# S7CAS-PLEIADES-CARTE-MERE_P07_ETH.net
KiCad netlist of a schematic drawn in Altium Designer
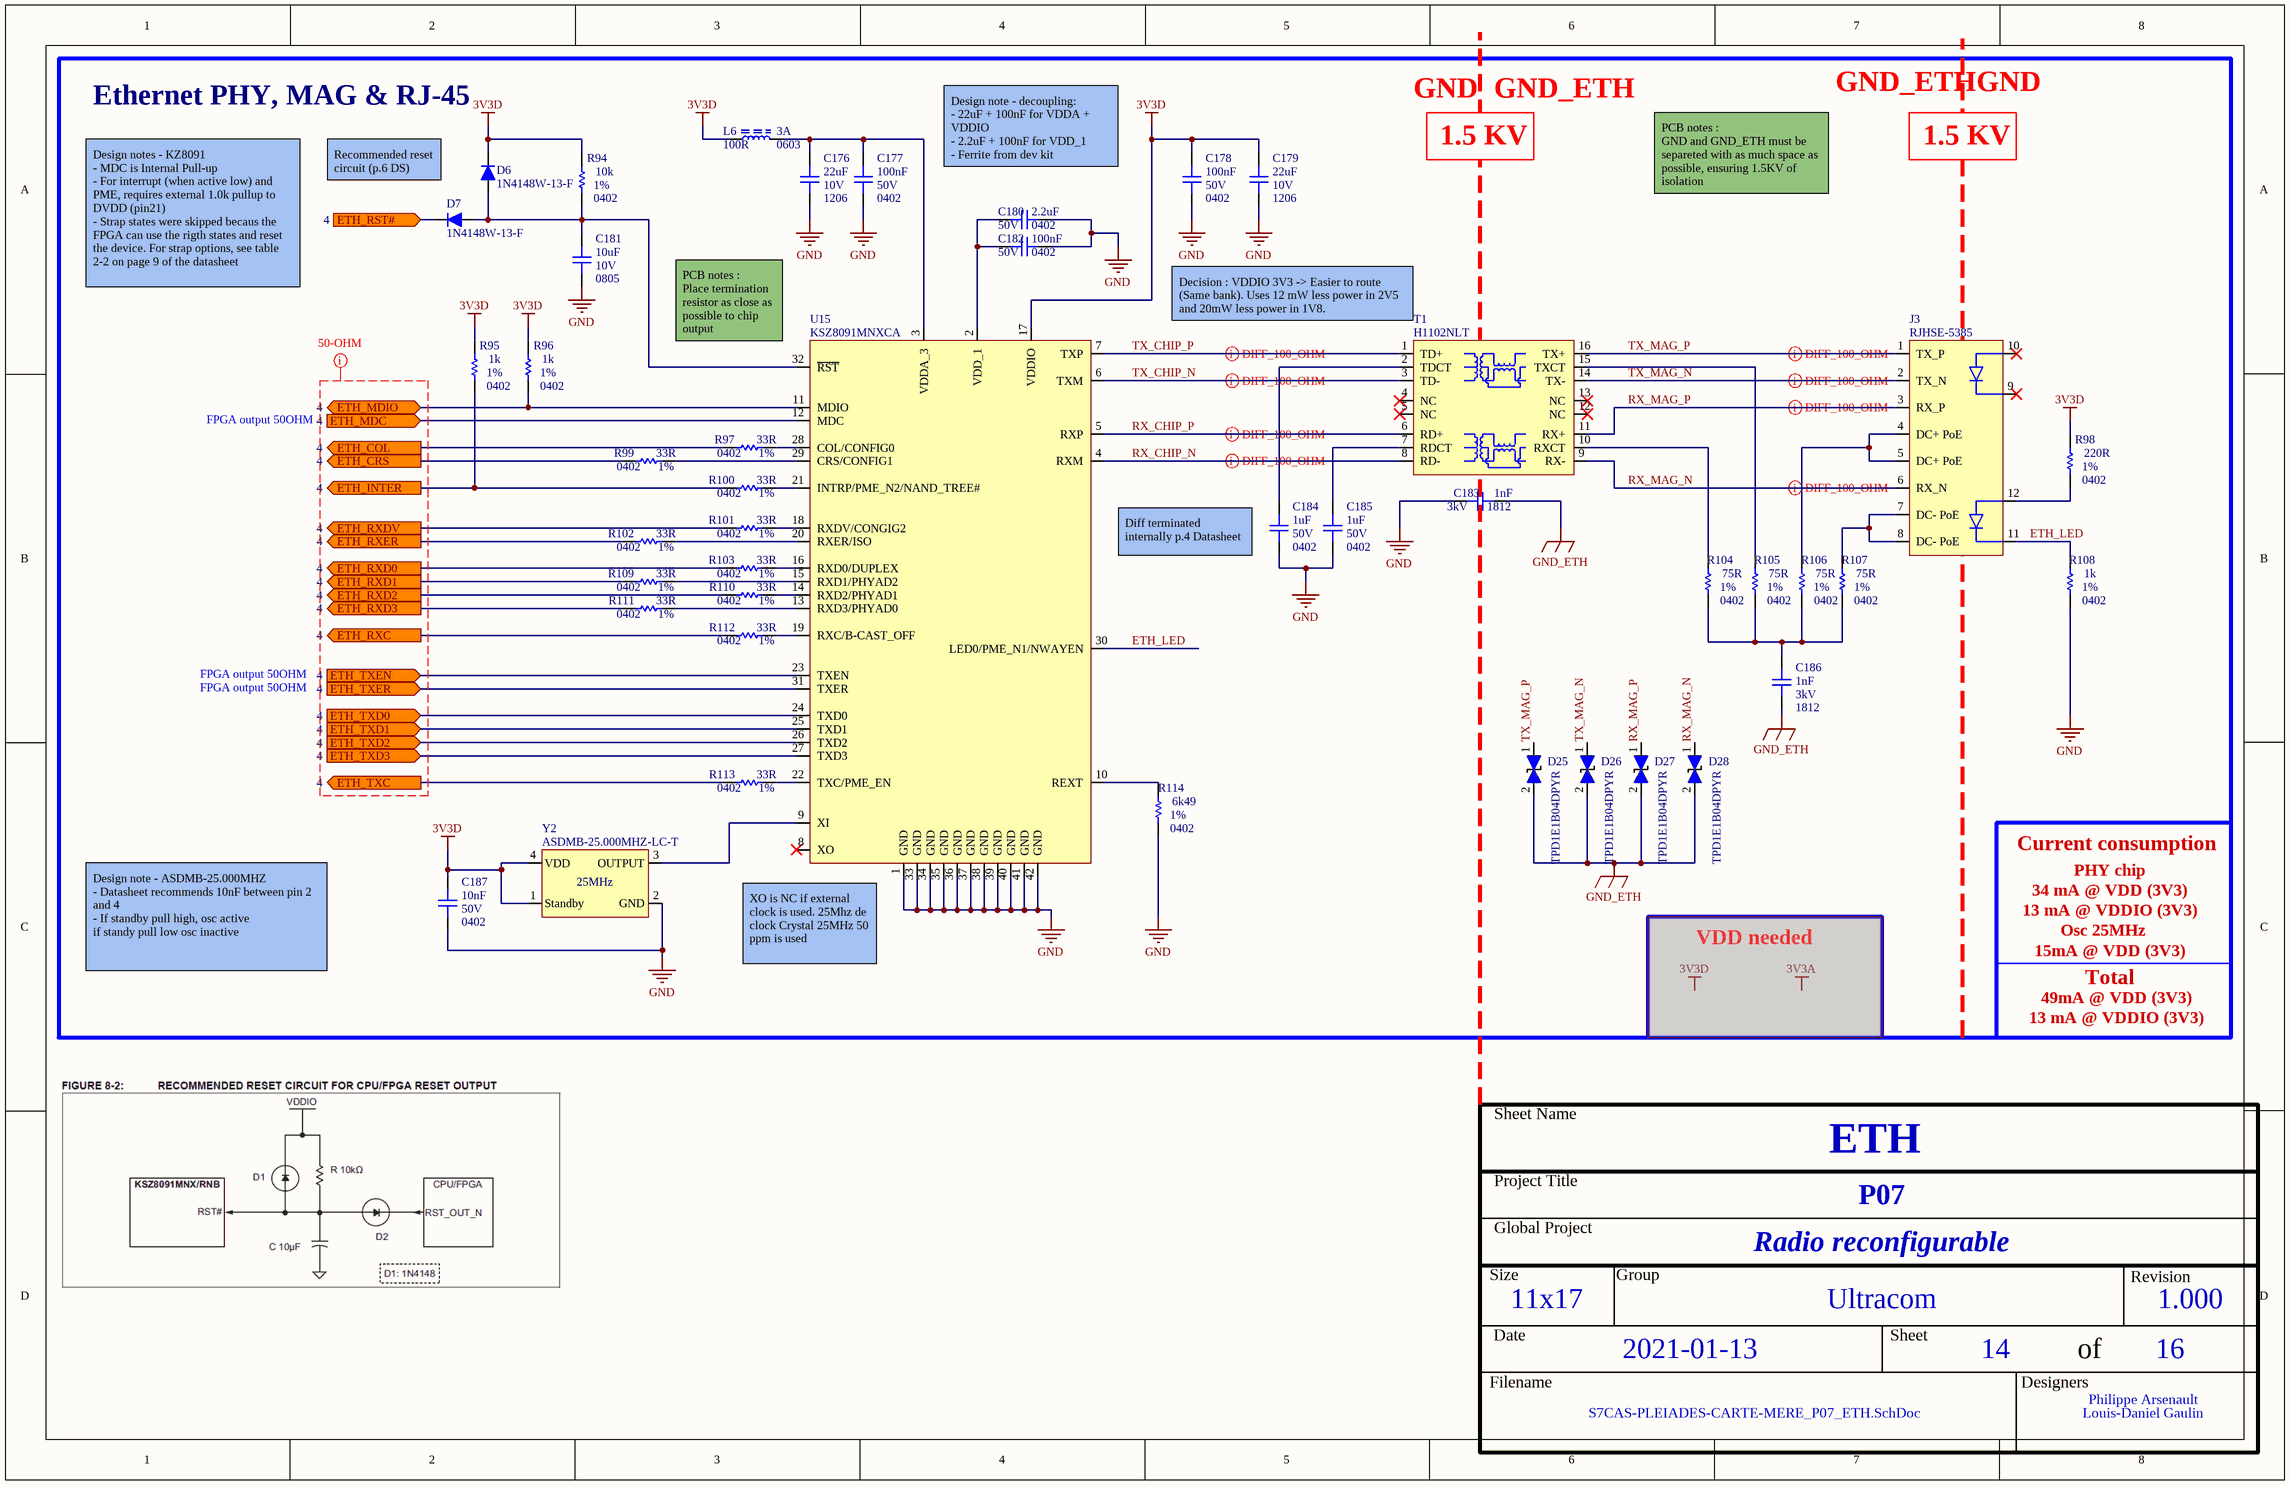
[diagram p0: S7CAS-PLEIADES-CARTE-MERE_P07_ETH.SchDoc]

(export (version "E")
  (design (tool "Eeschema 10.0.6"))
  (components
    (comp (ref "C176")
      (value "22uF")
      (footprint "CAP_1206")
      (description "CAP - 1206")
      (fields
        (field (name "VOLTAGE") "10V")
        (field (name "PACKAGE") "1206")
        (field (name "CREATEDBY") "Jonathan Bouchard")
      )
      (libsource (lib "S7CAS_LIB2021") (part "CAP - 1206"))
    )
    (comp (ref "C177")
      (value "100nF")
      (footprint "CAP_0402")
      (description "CAP - 0402")
      (fields
        (field (name "VOLTAGE") "50V")
        (field (name "PACKAGE") "0402")
        (field (name "CREATEDBY") "Jonathan Bouchard")
      )
      (libsource (lib "S7CAS_LIB2021") (part "CAP - 0402"))
    )
    (comp (ref "C178")
      (value "100nF")
      (footprint "CAP_0402")
      (description "CAP - 0402")
      (fields
        (field (name "VOLTAGE") "50V")
        (field (name "PACKAGE") "0402")
        (field (name "CREATEDBY") "Jonathan Bouchard")
      )
      (libsource (lib "S7CAS_LIB2021") (part "CAP - 0402"))
    )
    (comp (ref "C179")
      (value "22uF")
      (footprint "CAP_1206")
      (description "CAP - 1206")
      (fields
        (field (name "VOLTAGE") "10V")
        (field (name "PACKAGE") "1206")
        (field (name "CREATEDBY") "Jonathan Bouchard")
      )
      (libsource (lib "S7CAS_LIB2021") (part "CAP - 1206"))
    )
    (comp (ref "C180")
      (value "2.2uF")
      (footprint "CAP_0402")
      (description "CAP - 0402")
      (fields
        (field (name "VOLTAGE") "50V")
        (field (name "PACKAGE") "0402")
        (field (name "CREATEDBY") "Jonathan Bouchard")
      )
      (libsource (lib "S7CAS_LIB2021") (part "CAP - 0402"))
    )
    (comp (ref "C181")
      (value "10uF")
      (footprint "CAP_0805")
      (description "CAP - 0805")
      (fields
        (field (name "MFG") "CL21B106KPQNNNE")
        (field (name "VOLTAGE") "10V")
        (field (name "PACKAGE") "0805")
        (field (name "CREATEDBY") "Jonathan Bouchard")
      )
      (libsource (lib "S7CAS_LIB2021") (part "CAP - 0805"))
    )
    (comp (ref "C182")
      (value "100nF")
      (footprint "CAP_0402")
      (description "CAP - 0402")
      (fields
        (field (name "VOLTAGE") "50V")
        (field (name "PACKAGE") "0402")
        (field (name "CREATEDBY") "Jonathan Bouchard")
      )
      (libsource (lib "S7CAS_LIB2021") (part "CAP - 0402"))
    )
    (comp (ref "C183")
      (value "1nF")
      (footprint "CAP_1812")
      (description "CAP - 1812")
      (fields
        (field (name "MFG PART NUMBER") "1812HC102MAT1A")
        (field (name "VOLTAGE") "3kV")
        (field (name "PACKAGE") "1812")
        (field (name "CREATEDBY") "Jonathan Bouchard")
      )
      (libsource (lib "S7CAS_P07") (part "CAP - 1812"))
    )
    (comp (ref "C184")
      (value "1uF")
      (footprint "CAP_0402")
      (description "CAP - 0402")
      (fields
        (field (name "VOLTAGE") "50V")
        (field (name "PACKAGE") "0402")
        (field (name "CREATEDBY") "Jonathan Bouchard")
      )
      (libsource (lib "S7CAS_LIB2021") (part "CAP - 0402"))
    )
    (comp (ref "C185")
      (value "1uF")
      (footprint "CAP_0402")
      (description "CAP - 0402")
      (fields
        (field (name "VOLTAGE") "50V")
        (field (name "PACKAGE") "0402")
        (field (name "CREATEDBY") "Jonathan Bouchard")
      )
      (libsource (lib "S7CAS_LIB2021") (part "CAP - 0402"))
    )
    (comp (ref "C186")
      (value "1nF")
      (footprint "CAP_1812")
      (description "CAP - 1812")
      (fields
        (field (name "MFG PART NUMBER") "1812HC102MAT1A")
        (field (name "VOLTAGE") "3kV")
        (field (name "PACKAGE") "1812")
        (field (name "CREATEDBY") "Jonathan Bouchard")
      )
      (libsource (lib "S7CAS_P07") (part "CAP - 1812"))
    )
    (comp (ref "C187")
      (value "10nF")
      (footprint "CAP_0402")
      (description "CAP - 0402")
      (fields
        (field (name "VOLTAGE") "50V")
        (field (name "PACKAGE") "0402")
        (field (name "CREATEDBY") "Jonathan Bouchard")
      )
      (libsource (lib "S7CAS_LIB2021") (part "CAP - 0402"))
    )
    (comp (ref "D6")
      (value "1N4148W-13-F")
      (footprint "SOD123_DIO")
      (description "1N4148")
      (fields (field (name "COPYRIGHT") "Copyright (C) 2018 Accelerated Designs. All rights reserved"))
      (libsource (lib "S7CAS_P07") (part "DIO_1N4148W-13-F"))
    )
    (comp (ref "D7")
      (value "1N4148W-13-F")
      (footprint "SOD123_DIO")
      (description "1N4148")
      (fields (field (name "COPYRIGHT") "Copyright (C) 2018 Accelerated Designs. All rights reserved"))
      (libsource (lib "S7CAS_P07") (part "DIO_1N4148W-13-F"))
    )
    (comp (ref "D25")
      (value "TPD1E1B04DPYR")
      (footprint "TVS_DATA_TPD1E1B04DPYR")
      (description "TVS - TVS DIODE 3.6V 8.5V - 0402")
      (fields
        (field (name "CREATEDBY/DATE") "Keven Deslandes - 2018/10/19")
        (field (name "VERIFIEDBY") "Caroline Paulin - 28 janv 2019")
      )
      (libsource (lib "S7CAS_LIB2021") (part "TVS_DATA_TPD1E1B04DPYR"))
    )
    (comp (ref "D26")
      (value "TPD1E1B04DPYR")
      (footprint "TVS_DATA_TPD1E1B04DPYR")
      (description "TVS - TVS DIODE 3.6V 8.5V - 0402")
      (fields
        (field (name "CREATEDBY/DATE") "Keven Deslandes - 2018/10/19")
        (field (name "VERIFIEDBY") "Caroline Paulin - 28 janv 2019")
      )
      (libsource (lib "S7CAS_LIB2021") (part "TVS_DATA_TPD1E1B04DPYR"))
    )
    (comp (ref "D27")
      (value "TPD1E1B04DPYR")
      (footprint "TVS_DATA_TPD1E1B04DPYR")
      (description "TVS - TVS DIODE 3.6V 8.5V - 0402")
      (fields
        (field (name "CREATEDBY/DATE") "Keven Deslandes - 2018/10/19")
        (field (name "VERIFIEDBY") "Caroline Paulin - 28 janv 2019")
      )
      (libsource (lib "S7CAS_LIB2021") (part "TVS_DATA_TPD1E1B04DPYR"))
    )
    (comp (ref "D28")
      (value "TPD1E1B04DPYR")
      (footprint "TVS_DATA_TPD1E1B04DPYR")
      (description "TVS - TVS DIODE 3.6V 8.5V - 0402")
      (fields
        (field (name "CREATEDBY/DATE") "Keven Deslandes - 2018/10/19")
        (field (name "VERIFIEDBY") "Caroline Paulin - 28 janv 2019")
      )
      (libsource (lib "S7CAS_LIB2021") (part "TVS_DATA_TPD1E1B04DPYR"))
    )
    (comp (ref "J3")
      (value "RJHSE-5385")
      (footprint "CONN_ETHERNET_RJHSE-5385")
      (description "CONN - MOD JACK RJ45 R/A ETHERNET - TH")
      (fields (field (name "MFG") "Amphenol") (field (name "CREATEDBY") "Jonathan Bouchard"))
      (libsource (lib "S7CAS_LIB2021") (part "CONN_ETHERNET_RJHSE-5385"))
    )
    (comp (ref "L6")
      (value "100R")
      (footprint "FER_0603")
      (description "FER - 0603")
      (fields
        (field (name "CURRENT") "3A")
        (field (name "PACKAGE") "0603")
        (field (name "CREATEDBY") "Jonathan Bouchard")
      )
      (libsource (lib "S7CAS_LIB2021") (part "FER - 0603"))
    )
    (comp (ref "R94")
      (value "10k")
      (footprint "RES_0402")
      (description "RES - 0402")
      (fields
        (field (name "VOLTAGE") "50V")
        (field (name "POWER") "1/16W")
        (field (name "PACKAGE") "0402")
        (field (name "PRECISION") "1%")
        (field (name "CREATEDBY") "Jonathan Bouchard")
      )
      (libsource (lib "S7CAS_LIB2021") (part "RES - 0402"))
    )
    (comp (ref "R95")
      (value "1k")
      (footprint "RES_0402")
      (description "RES - 0402")
      (fields
        (field (name "VOLTAGE") "50V")
        (field (name "POWER") "1/16W")
        (field (name "PACKAGE") "0402")
        (field (name "PRECISION") "1%")
        (field (name "CREATEDBY") "Jonathan Bouchard")
      )
      (libsource (lib "S7CAS_LIB2021") (part "RES - 0402"))
    )
    (comp (ref "R96")
      (value "1k")
      (footprint "RES_0402")
      (description "RES - 0402")
      (fields
        (field (name "VOLTAGE") "50V")
        (field (name "POWER") "1/16W")
        (field (name "PACKAGE") "0402")
        (field (name "PRECISION") "1%")
        (field (name "CREATEDBY") "Jonathan Bouchard")
      )
      (libsource (lib "S7CAS_LIB2021") (part "RES - 0402"))
    )
    (comp (ref "R97")
      (value "33R")
      (footprint "RES_0402")
      (description "RES - 0402")
      (fields
        (field (name "VOLTAGE") "50V")
        (field (name "POWER") "1/16W")
        (field (name "PACKAGE") "0402")
        (field (name "PRECISION") "1%")
        (field (name "CREATEDBY") "Jonathan Bouchard")
      )
      (libsource (lib "S7CAS_LIB2021") (part "RES - 0402"))
    )
    (comp (ref "R98")
      (value "220R")
      (footprint "RES_0402")
      (description "RES - 0402")
      (fields
        (field (name "VOLTAGE") "50V")
        (field (name "POWER") "1/16W")
        (field (name "PACKAGE") "0402")
        (field (name "PRECISION") "1%")
        (field (name "CREATEDBY") "Jonathan Bouchard")
      )
      (libsource (lib "S7CAS_LIB2021") (part "RES - 0402"))
    )
    (comp (ref "R99")
      (value "33R")
      (footprint "RES_0402")
      (description "RES - 0402")
      (fields
        (field (name "VOLTAGE") "50V")
        (field (name "POWER") "1/16W")
        (field (name "PACKAGE") "0402")
        (field (name "PRECISION") "1%")
        (field (name "CREATEDBY") "Jonathan Bouchard")
      )
      (libsource (lib "S7CAS_LIB2021") (part "RES - 0402"))
    )
    (comp (ref "R100")
      (value "33R")
      (footprint "RES_0402")
      (description "RES - 0402")
      (fields
        (field (name "VOLTAGE") "50V")
        (field (name "POWER") "1/16W")
        (field (name "PACKAGE") "0402")
        (field (name "PRECISION") "1%")
        (field (name "CREATEDBY") "Jonathan Bouchard")
      )
      (libsource (lib "S7CAS_LIB2021") (part "RES - 0402"))
    )
    (comp (ref "R101")
      (value "33R")
      (footprint "RES_0402")
      (description "RES - 0402")
      (fields
        (field (name "VOLTAGE") "50V")
        (field (name "POWER") "1/16W")
        (field (name "PACKAGE") "0402")
        (field (name "PRECISION") "1%")
        (field (name "CREATEDBY") "Jonathan Bouchard")
      )
      (libsource (lib "S7CAS_LIB2021") (part "RES - 0402"))
    )
    (comp (ref "R102")
      (value "33R")
      (footprint "RES_0402")
      (description "RES - 0402")
      (fields
        (field (name "VOLTAGE") "50V")
        (field (name "POWER") "1/16W")
        (field (name "PACKAGE") "0402")
        (field (name "PRECISION") "1%")
        (field (name "CREATEDBY") "Jonathan Bouchard")
      )
      (libsource (lib "S7CAS_LIB2021") (part "RES - 0402"))
    )
    (comp (ref "R103")
      (value "33R")
      (footprint "RES_0402")
      (description "RES - 0402")
      (fields
        (field (name "VOLTAGE") "50V")
        (field (name "POWER") "1/16W")
        (field (name "PACKAGE") "0402")
        (field (name "PRECISION") "1%")
        (field (name "CREATEDBY") "Jonathan Bouchard")
      )
      (libsource (lib "S7CAS_LIB2021") (part "RES - 0402"))
    )
    (comp (ref "R104")
      (value "75R")
      (footprint "RES_0402")
      (description "RES - 0402")
      (fields
        (field (name "VOLTAGE") "50V")
        (field (name "POWER") "1/16W")
        (field (name "PACKAGE") "0402")
        (field (name "PRECISION") "1%")
        (field (name "CREATEDBY") "Jonathan Bouchard")
      )
      (libsource (lib "S7CAS_LIB2021") (part "RES - 0402"))
    )
    (comp (ref "R105")
      (value "75R")
      (footprint "RES_0402")
      (description "RES - 0402")
      (fields
        (field (name "VOLTAGE") "50V")
        (field (name "POWER") "1/16W")
        (field (name "PACKAGE") "0402")
        (field (name "PRECISION") "1%")
        (field (name "CREATEDBY") "Jonathan Bouchard")
      )
      (libsource (lib "S7CAS_LIB2021") (part "RES - 0402"))
    )
    (comp (ref "R106")
      (value "75R")
      (footprint "RES_0402")
      (description "RES - 0402")
      (fields
        (field (name "VOLTAGE") "50V")
        (field (name "POWER") "1/16W")
        (field (name "PACKAGE") "0402")
        (field (name "PRECISION") "1%")
        (field (name "CREATEDBY") "Jonathan Bouchard")
      )
      (libsource (lib "S7CAS_LIB2021") (part "RES - 0402"))
    )
    (comp (ref "R107")
      (value "75R")
      (footprint "RES_0402")
      (description "RES - 0402")
      (fields
        (field (name "VOLTAGE") "50V")
        (field (name "POWER") "1/16W")
        (field (name "PACKAGE") "0402")
        (field (name "PRECISION") "1%")
        (field (name "CREATEDBY") "Jonathan Bouchard")
      )
      (libsource (lib "S7CAS_LIB2021") (part "RES - 0402"))
    )
    (comp (ref "R108")
      (value "1k")
      (footprint "RES_0402")
      (description "RES - 0402")
      (fields
        (field (name "VOLTAGE") "50V")
        (field (name "POWER") "1/16W")
        (field (name "PACKAGE") "0402")
        (field (name "PRECISION") "1%")
        (field (name "CREATEDBY") "Jonathan Bouchard")
      )
      (libsource (lib "S7CAS_LIB2021") (part "RES - 0402"))
    )
    (comp (ref "R109")
      (value "33R")
      (footprint "RES_0402")
      (description "RES - 0402")
      (fields
        (field (name "VOLTAGE") "50V")
        (field (name "POWER") "1/16W")
        (field (name "PACKAGE") "0402")
        (field (name "PRECISION") "1%")
        (field (name "CREATEDBY") "Jonathan Bouchard")
      )
      (libsource (lib "S7CAS_LIB2021") (part "RES - 0402"))
    )
    (comp (ref "R110")
      (value "33R")
      (footprint "RES_0402")
      (description "RES - 0402")
      (fields
        (field (name "VOLTAGE") "50V")
        (field (name "POWER") "1/16W")
        (field (name "PACKAGE") "0402")
        (field (name "PRECISION") "1%")
        (field (name "CREATEDBY") "Jonathan Bouchard")
      )
      (libsource (lib "S7CAS_LIB2021") (part "RES - 0402"))
    )
    (comp (ref "R111")
      (value "33R")
      (footprint "RES_0402")
      (description "RES - 0402")
      (fields
        (field (name "VOLTAGE") "50V")
        (field (name "POWER") "1/16W")
        (field (name "PACKAGE") "0402")
        (field (name "PRECISION") "1%")
        (field (name "CREATEDBY") "Jonathan Bouchard")
      )
      (libsource (lib "S7CAS_LIB2021") (part "RES - 0402"))
    )
    (comp (ref "R112")
      (value "33R")
      (footprint "RES_0402")
      (description "RES - 0402")
      (fields
        (field (name "VOLTAGE") "50V")
        (field (name "POWER") "1/16W")
        (field (name "PACKAGE") "0402")
        (field (name "PRECISION") "1%")
        (field (name "CREATEDBY") "Jonathan Bouchard")
      )
      (libsource (lib "S7CAS_LIB2021") (part "RES - 0402"))
    )
    (comp (ref "R113")
      (value "33R")
      (footprint "RES_0402")
      (description "RES - 0402")
      (fields
        (field (name "VOLTAGE") "50V")
        (field (name "POWER") "1/16W")
        (field (name "PACKAGE") "0402")
        (field (name "PRECISION") "1%")
        (field (name "CREATEDBY") "Jonathan Bouchard")
      )
      (libsource (lib "S7CAS_LIB2021") (part "RES - 0402"))
    )
    (comp (ref "R114")
      (value "6k49")
      (footprint "RES_0402")
      (description "RES - 0402")
      (fields
        (field (name "VOLTAGE") "50V")
        (field (name "POWER") "1/16W")
        (field (name "PACKAGE") "0402")
        (field (name "PRECISION") "1%")
        (field (name "CREATEDBY") "Jonathan Bouchard")
      )
      (libsource (lib "S7CAS_LIB2021") (part "RES - 0402"))
    )
    (comp (ref "T1")
      (value "H1102NLT")
      (footprint "TRANSFO_H1102NLT")
      (description "TRANSFO - ETHERNET 10/100B-TX - SMD-16")
      (fields (field (name "MFG") "Pulse Eng.") (field (name "CREATEDBY") "Jonathan Bouchard"))
      (libsource (lib "S7CAS_LIB2021") (part "TRANSFO_H1102NLT"))
    )
    (comp (ref "U15")
      (value "KSZ8091MNXCA")
      (footprint "COM_ETH_PHY_KSZ8091MNXCA")
      (description "COM - ETHERNET PHY 10/100 - QFN-32")
      (fields
        (field (name "VOLTAGE") "1.8V, 2.5V, 3.3V")
        (field (name "MFG") "Micrel")
        (field (name "CREATEDBY") "Jonathan Bouchard")
      )
      (libsource (lib "S7CAS_LIB2021") (part "COM_ETH_PHY_KSZ8091MNXCA"))
    )
    (comp (ref "Y2")
      (value "ASDMB-25.000MHZ-LC-T")
      (footprint "OSC_ASDMB-25.000MHZ-LC-T")
      (description "OSC - 25MHz XO (Standard) LVCMOS - 4-SMD, No Lead")
      (fields
        (field (name "TOLERANCE") "±50ppm")
        (field (name "CREATEDBY/DATE") "Joël Lemay 2019-03-29")
        (field (name "VERIFIEDBY") "C. Paulin - 29 mai 2019")
      )
      (libsource (lib "S7CAS_LIB2021") (part "OSC_ASDMB-25.000MHZ-LC-T"))
    )
  )
  (nets
    (net (code "1") (name "/ETH_COL") (class "Default")
      (node (ref "R97") (pin "2") (pinfunction "2_2") (pintype "passive"))
    )
    (net (code "2") (name "/ETH_CRS") (class "Default")
      (node (ref "R99") (pin "2") (pinfunction "2_2") (pintype "passive"))
    )
    (net (code "3") (name "/ETH_INTER") (class "Default")
      (node (ref "R100") (pin "2") (pinfunction "2_2") (pintype "passive"))
      (node (ref "R95") (pin "1") (pinfunction "1_1") (pintype "passive"))
    )
    (net (code "4") (name "/ETH_LED") (class "Default")
      (node (ref "J3") (pin "11") (pinfunction "LED2_K_11") (pintype "passive"))
      (node (ref "R108") (pin "2") (pinfunction "2_2") (pintype "passive"))
      (node (ref "U15") (pin "30") (pinfunction "LED0/PME_N1/NWAYEN_30") (pintype "passive"))
    )
    (net (code "5") (name "/ETH_MDC") (class "Default")
      (node (ref "U15") (pin "12") (pinfunction "MDC_12") (pintype "passive"))
    )
    (net (code "6") (name "/ETH_MDIO") (class "Default")
      (node (ref "R96") (pin "1") (pinfunction "1_1") (pintype "passive"))
      (node (ref "U15") (pin "11") (pinfunction "MDIO_11") (pintype "passive"))
    )
    (net (code "7") (name "/ETH_RST#") (class "Default")
      (node (ref "D7") (pin "1") (pinfunction "1_1") (pintype "passive"))
    )
    (net (code "8") (name "/ETH_RXC") (class "Default")
      (node (ref "R112") (pin "2") (pinfunction "2_2") (pintype "passive"))
    )
    (net (code "9") (name "/ETH_RXD0") (class "Default")
      (node (ref "R103") (pin "2") (pinfunction "2_2") (pintype "passive"))
    )
    (net (code "10") (name "/ETH_RXD1") (class "Default")
      (node (ref "R109") (pin "2") (pinfunction "2_2") (pintype "passive"))
    )
    (net (code "11") (name "/ETH_RXD2") (class "Default")
      (node (ref "R110") (pin "2") (pinfunction "2_2") (pintype "passive"))
    )
    (net (code "12") (name "/ETH_RXD3") (class "Default")
      (node (ref "R111") (pin "2") (pinfunction "2_2") (pintype "passive"))
    )
    (net (code "13") (name "/ETH_RXDV") (class "Default")
      (node (ref "R101") (pin "2") (pinfunction "2_2") (pintype "passive"))
    )
    (net (code "14") (name "/ETH_RXER") (class "Default")
      (node (ref "R102") (pin "2") (pinfunction "2_2") (pintype "passive"))
    )
    (net (code "15") (name "/ETH_TXC") (class "Default")
      (node (ref "R113") (pin "2") (pinfunction "2_2") (pintype "passive"))
    )
    (net (code "16") (name "/ETH_TXD0") (class "Default")
      (node (ref "U15") (pin "24") (pinfunction "TXD0_24") (pintype "passive"))
    )
    (net (code "17") (name "/ETH_TXD1") (class "Default")
      (node (ref "U15") (pin "25") (pinfunction "TXD1_25") (pintype "passive"))
    )
    (net (code "18") (name "/ETH_TXD2") (class "Default")
      (node (ref "U15") (pin "26") (pinfunction "TXD2_26") (pintype "passive"))
    )
    (net (code "19") (name "/ETH_TXD3") (class "Default")
      (node (ref "U15") (pin "27") (pinfunction "TXD3_27") (pintype "passive"))
    )
    (net (code "20") (name "/ETH_TXEN") (class "Default")
      (node (ref "U15") (pin "23") (pinfunction "TXEN_23") (pintype "passive"))
    )
    (net (code "21") (name "/ETH_TXER") (class "Default")
      (node (ref "U15") (pin "31") (pinfunction "TXER_31") (pintype "passive"))
    )
    (net (code "22") (name "/RX_CHIP_N") (class "Default")
      (node (ref "T1") (pin "8") (pinfunction "RD-_8") (pintype "passive"))
      (node (ref "U15") (pin "4") (pinfunction "RXM_4") (pintype "passive"))
    )
    (net (code "23") (name "/RX_CHIP_P") (class "Default")
      (node (ref "T1") (pin "6") (pinfunction "RD+_6") (pintype "passive"))
      (node (ref "U15") (pin "5") (pinfunction "RXP_5") (pintype "passive"))
    )
    (net (code "24") (name "/RX_MAG_N") (class "Default")
      (node (ref "D28") (pin "1") (pinfunction "i/o_1") (pintype "passive"))
      (node (ref "J3") (pin "6") (pinfunction "RX_N_6") (pintype "passive"))
      (node (ref "T1") (pin "9") (pinfunction "RX-_9") (pintype "passive"))
    )
    (net (code "25") (name "/RX_MAG_P") (class "Default")
      (node (ref "D27") (pin "1") (pinfunction "i/o_1") (pintype "passive"))
      (node (ref "J3") (pin "3") (pinfunction "RX_P_3") (pintype "passive"))
      (node (ref "T1") (pin "11") (pinfunction "RX+_11") (pintype "passive"))
    )
    (net (code "26") (name "/TX_CHIP_N") (class "Default")
      (node (ref "T1") (pin "3") (pinfunction "TD-_3") (pintype "passive"))
      (node (ref "U15") (pin "6") (pinfunction "TXM_6") (pintype "passive"))
    )
    (net (code "27") (name "/TX_CHIP_P") (class "Default")
      (node (ref "T1") (pin "1") (pinfunction "TD+_1") (pintype "passive"))
      (node (ref "U15") (pin "7") (pinfunction "TXP_7") (pintype "passive"))
    )
    (net (code "28") (name "/TX_MAG_N") (class "Default")
      (node (ref "D26") (pin "1") (pinfunction "i/o_1") (pintype "passive"))
      (node (ref "J3") (pin "2") (pinfunction "TX_N_2") (pintype "passive"))
      (node (ref "T1") (pin "14") (pinfunction "TX-_14") (pintype "passive"))
    )
    (net (code "29") (name "/TX_MAG_P") (class "Default")
      (node (ref "D25") (pin "1") (pinfunction "i/o_1") (pintype "passive"))
      (node (ref "J3") (pin "1") (pinfunction "TX_P_1") (pintype "passive"))
      (node (ref "T1") (pin "16") (pinfunction "TX+_16") (pintype "passive"))
    )
    (net (code "31") (name "3V3D") (class "Default")
      (node (ref "C178") (pin "2") (pinfunction "2_2") (pintype "passive"))
      (node (ref "C179") (pin "2") (pinfunction "2_2") (pintype "passive"))
      (node (ref "C187") (pin "2") (pinfunction "2_2") (pintype "passive"))
      (node (ref "D6") (pin "1") (pinfunction "1_1") (pintype "passive"))
      (node (ref "L6") (pin "2") (pinfunction "2_2") (pintype "passive"))
      (node (ref "R94") (pin "2") (pinfunction "2_2") (pintype "passive"))
      (node (ref "R95") (pin "2") (pinfunction "2_2") (pintype "passive"))
      (node (ref "R96") (pin "2") (pinfunction "2_2") (pintype "passive"))
      (node (ref "R98") (pin "2") (pinfunction "2_2") (pintype "passive"))
      (node (ref "U15") (pin "17") (pinfunction "VDDIO_17") (pintype "power_in"))
      (node (ref "Y2") (pin "1") (pinfunction "Standby_1") (pintype "passive"))
      (node (ref "Y2") (pin "4") (pinfunction "VDD_4") (pintype "passive"))
    )
    (net (code "32") (name "GND") (class "Default")
      (node (ref "C176") (pin "1") (pinfunction "1_1") (pintype "passive"))
      (node (ref "C177") (pin "1") (pinfunction "1_1") (pintype "passive"))
      (node (ref "C178") (pin "1") (pinfunction "1_1") (pintype "passive"))
      (node (ref "C179") (pin "1") (pinfunction "1_1") (pintype "passive"))
      (node (ref "C180") (pin "1") (pinfunction "1_1") (pintype "passive"))
      (node (ref "C181") (pin "1") (pinfunction "1_1") (pintype "passive"))
      (node (ref "C182") (pin "1") (pinfunction "1_1") (pintype "passive"))
      (node (ref "C183") (pin "2") (pinfunction "2_2") (pintype "passive"))
      (node (ref "C184") (pin "1") (pinfunction "1_1") (pintype "passive"))
      (node (ref "C185") (pin "1") (pinfunction "1_1") (pintype "passive"))
      (node (ref "C187") (pin "1") (pinfunction "1_1") (pintype "passive"))
      (node (ref "R108") (pin "1") (pinfunction "1_1") (pintype "passive"))
      (node (ref "R114") (pin "1") (pinfunction "1_1") (pintype "passive"))
      (node (ref "U15") (pin "1") (pinfunction "GND_1") (pintype "passive"))
      (node (ref "U15") (pin "33") (pinfunction "GND_33") (pintype "passive"))
      (node (ref "U15") (pin "34") (pinfunction "GND_34") (pintype "passive"))
      (node (ref "U15") (pin "35") (pinfunction "GND_35") (pintype "passive"))
      (node (ref "U15") (pin "36") (pinfunction "GND_36") (pintype "passive"))
      (node (ref "U15") (pin "37") (pinfunction "GND_37") (pintype "passive"))
      (node (ref "U15") (pin "38") (pinfunction "GND_38") (pintype "passive"))
      (node (ref "U15") (pin "39") (pinfunction "GND_39") (pintype "passive"))
      (node (ref "U15") (pin "40") (pinfunction "GND_40") (pintype "passive"))
      (node (ref "U15") (pin "41") (pinfunction "GND_41") (pintype "passive"))
      (node (ref "U15") (pin "42") (pinfunction "GND_42") (pintype "passive"))
      (node (ref "Y2") (pin "2") (pinfunction "GND_2") (pintype "passive"))
    )
    (net (code "33") (name "GND_ETH") (class "Default")
      (node (ref "C183") (pin "1") (pinfunction "1_1") (pintype "passive"))
      (node (ref "C186") (pin "2") (pinfunction "2_2") (pintype "passive"))
      (node (ref "D25") (pin "2") (pinfunction "i/o_2") (pintype "passive"))
      (node (ref "D26") (pin "2") (pinfunction "i/o_2") (pintype "passive"))
      (node (ref "D27") (pin "2") (pinfunction "i/o_2") (pintype "passive"))
      (node (ref "D28") (pin "2") (pinfunction "i/o_2") (pintype "passive"))
    )
    (net (code "34") (name "Net-(C186-Pad1)") (class "Default")
      (node (ref "C186") (pin "1") (pinfunction "1_1") (pintype "passive"))
      (node (ref "R104") (pin "1") (pinfunction "1_1") (pintype "passive"))
      (node (ref "R105") (pin "1") (pinfunction "1_1") (pintype "passive"))
      (node (ref "R106") (pin "1") (pinfunction "1_1") (pintype "passive"))
      (node (ref "R107") (pin "1") (pinfunction "1_1") (pintype "passive"))
    )
    (net (code "35") (name "Net-(J3-DC+_PoE-Pad4)") (class "Default")
      (node (ref "J3") (pin "4") (pinfunction "DC+_PoE_4") (pintype "passive"))
      (node (ref "J3") (pin "5") (pinfunction "DC+_PoE_5") (pintype "passive"))
      (node (ref "R106") (pin "2") (pinfunction "2_2") (pintype "passive"))
    )
    (net (code "36") (name "Net-(J3-DC-_PoE-Pad7)") (class "Default")
      (node (ref "J3") (pin "7") (pinfunction "DC-_PoE_7") (pintype "passive"))
      (node (ref "J3") (pin "8") (pinfunction "DC-_PoE_8") (pintype "passive"))
      (node (ref "R107") (pin "2") (pinfunction "2_2") (pintype "passive"))
    )
    (net (code "37") (name "Net-(J3-LED2_A)") (class "Default")
      (node (ref "J3") (pin "12") (pinfunction "LED2_A_12") (pintype "passive"))
      (node (ref "R98") (pin "1") (pinfunction "1_1") (pintype "passive"))
    )
    (net (code "38") (name "Net-(T1-RDCT)") (class "Default")
      (node (ref "C185") (pin "2") (pinfunction "2_2") (pintype "passive"))
      (node (ref "T1") (pin "7") (pinfunction "RDCT_7") (pintype "passive"))
    )
    (net (code "39") (name "Net-(T1-RXCT)") (class "Default")
      (node (ref "R104") (pin "2") (pinfunction "2_2") (pintype "passive"))
      (node (ref "T1") (pin "10") (pinfunction "RXCT_10") (pintype "passive"))
    )
    (net (code "40") (name "Net-(T1-TDCT)") (class "Default")
      (node (ref "C184") (pin "2") (pinfunction "2_2") (pintype "passive"))
      (node (ref "T1") (pin "2") (pinfunction "TDCT_2") (pintype "passive"))
    )
    (net (code "41") (name "Net-(T1-TXCT)") (class "Default")
      (node (ref "R105") (pin "2") (pinfunction "2_2") (pintype "passive"))
      (node (ref "T1") (pin "15") (pinfunction "TXCT_15") (pintype "passive"))
    )
    (net (code "42") (name "Net-(U15-COL{slash}CONFIG0)") (class "Default")
      (node (ref "R97") (pin "1") (pinfunction "1_1") (pintype "passive"))
      (node (ref "U15") (pin "28") (pinfunction "COL/CONFIG0_28") (pintype "passive"))
    )
    (net (code "43") (name "Net-(U15-CRS{slash}CONFIG1)") (class "Default")
      (node (ref "R99") (pin "1") (pinfunction "1_1") (pintype "passive"))
      (node (ref "U15") (pin "29") (pinfunction "CRS/CONFIG1_29") (pintype "passive"))
    )
    (net (code "44") (name "Net-(U15-INTRP{slash}PME_N2{slash}NAND_TREE#)") (class "Default")
      (node (ref "R100") (pin "1") (pinfunction "1_1") (pintype "passive"))
      (node (ref "U15") (pin "21") (pinfunction "INTRP/PME_N2/NAND_TREE#_21") (pintype "passive"))
    )
    (net (code "45") (name "Net-(U15-REXT)") (class "Default")
      (node (ref "R114") (pin "2") (pinfunction "2_2") (pintype "passive"))
      (node (ref "U15") (pin "10") (pinfunction "REXT_10") (pintype "passive"))
    )
    (net (code "46") (name "Net-(U15-RST)") (class "Default")
      (node (ref "C181") (pin "2") (pinfunction "2_2") (pintype "passive"))
      (node (ref "D6") (pin "2") (pinfunction "2_2") (pintype "passive"))
      (node (ref "D7") (pin "2") (pinfunction "2_2") (pintype "passive"))
      (node (ref "R94") (pin "1") (pinfunction "1_1") (pintype "passive"))
      (node (ref "U15") (pin "32") (pinfunction "RST_32") (pintype "passive"))
    )
    (net (code "47") (name "Net-(U15-RXC{slash}B-CAST_OFF)") (class "Default")
      (node (ref "R112") (pin "1") (pinfunction "1_1") (pintype "passive"))
      (node (ref "U15") (pin "19") (pinfunction "RXC/B-CAST_OFF_19") (pintype "passive"))
    )
    (net (code "48") (name "Net-(U15-RXD0{slash}DUPLEX)") (class "Default")
      (node (ref "R103") (pin "1") (pinfunction "1_1") (pintype "passive"))
      (node (ref "U15") (pin "16") (pinfunction "RXD0/DUPLEX_16") (pintype "passive"))
    )
    (net (code "49") (name "Net-(U15-RXD1{slash}PHYAD2)") (class "Default")
      (node (ref "R109") (pin "1") (pinfunction "1_1") (pintype "passive"))
      (node (ref "U15") (pin "15") (pinfunction "RXD1/PHYAD2_15") (pintype "passive"))
    )
    (net (code "50") (name "Net-(U15-RXD2{slash}PHYAD1)") (class "Default")
      (node (ref "R110") (pin "1") (pinfunction "1_1") (pintype "passive"))
      (node (ref "U15") (pin "14") (pinfunction "RXD2/PHYAD1_14") (pintype "passive"))
    )
    (net (code "51") (name "Net-(U15-RXD3{slash}PHYAD0)") (class "Default")
      (node (ref "R111") (pin "1") (pinfunction "1_1") (pintype "passive"))
      (node (ref "U15") (pin "13") (pinfunction "RXD3/PHYAD0_13") (pintype "passive"))
    )
    (net (code "52") (name "Net-(U15-RXDV{slash}CONGIG2)") (class "Default")
      (node (ref "R101") (pin "1") (pinfunction "1_1") (pintype "passive"))
      (node (ref "U15") (pin "18") (pinfunction "RXDV/CONGIG2_18") (pintype "passive"))
    )
    (net (code "53") (name "Net-(U15-RXER{slash}ISO)") (class "Default")
      (node (ref "R102") (pin "1") (pinfunction "1_1") (pintype "passive"))
      (node (ref "U15") (pin "20") (pinfunction "RXER/ISO_20") (pintype "passive"))
    )
    (net (code "54") (name "Net-(U15-TXC{slash}PME_EN)") (class "Default")
      (node (ref "R113") (pin "1") (pinfunction "1_1") (pintype "passive"))
      (node (ref "U15") (pin "22") (pinfunction "TXC/PME_EN_22") (pintype "passive"))
    )
    (net (code "55") (name "Net-(U15-VDDA_3)") (class "Default")
      (node (ref "C176") (pin "2") (pinfunction "2_2") (pintype "passive"))
      (node (ref "C177") (pin "2") (pinfunction "2_2") (pintype "passive"))
      (node (ref "L6") (pin "1") (pinfunction "1_1") (pintype "passive"))
      (node (ref "U15") (pin "3") (pinfunction "VDDA_3_3") (pintype "power_in"))
    )
    (net (code "56") (name "Net-(U15-VDD_1)") (class "Default")
      (node (ref "C180") (pin "2") (pinfunction "2_2") (pintype "passive"))
      (node (ref "C182") (pin "2") (pinfunction "2_2") (pintype "passive"))
      (node (ref "U15") (pin "2") (pinfunction "VDD_1_2") (pintype "power_in"))
    )
    (net (code "57") (name "Net-(U15-XI)") (class "Default")
      (node (ref "U15") (pin "9") (pinfunction "XI_9") (pintype "passive"))
      (node (ref "Y2") (pin "3") (pinfunction "OUTPUT_3") (pintype "passive"))
    )
    (net (code "58") (name "unconnected-(J3-LED1_A-Pad10)") (class "Default")
      (node (ref "J3") (pin "10") (pinfunction "LED1_A_10") (pintype "passive+no_connect"))
    )
    (net (code "59") (name "unconnected-(J3-LED1_K-Pad9)") (class "Default")
      (node (ref "J3") (pin "9") (pinfunction "LED1_K_9") (pintype "passive+no_connect"))
    )
    (net (code "60") (name "unconnected-(T1-NC-Pad4)") (class "Default")
      (node (ref "T1") (pin "4") (pinfunction "NC_4") (pintype "passive+no_connect"))
    )
    (net (code "61") (name "unconnected-(T1-NC-Pad5)") (class "Default")
      (node (ref "T1") (pin "5") (pinfunction "NC_5") (pintype "passive+no_connect"))
    )
    (net (code "62") (name "unconnected-(T1-NC-Pad12)") (class "Default")
      (node (ref "T1") (pin "12") (pinfunction "NC_12") (pintype "passive+no_connect"))
    )
    (net (code "63") (name "unconnected-(T1-NC-Pad13)") (class "Default")
      (node (ref "T1") (pin "13") (pinfunction "NC_13") (pintype "passive+no_connect"))
    )
    (net (code "64") (name "unconnected-(U15-XO-Pad8)") (class "Default")
      (node (ref "U15") (pin "8") (pinfunction "XO_8") (pintype "passive+no_connect"))
    )
  )
)
